# lcd_breakout.net
KiCad netlist of a schematic drawn in Altium Designer
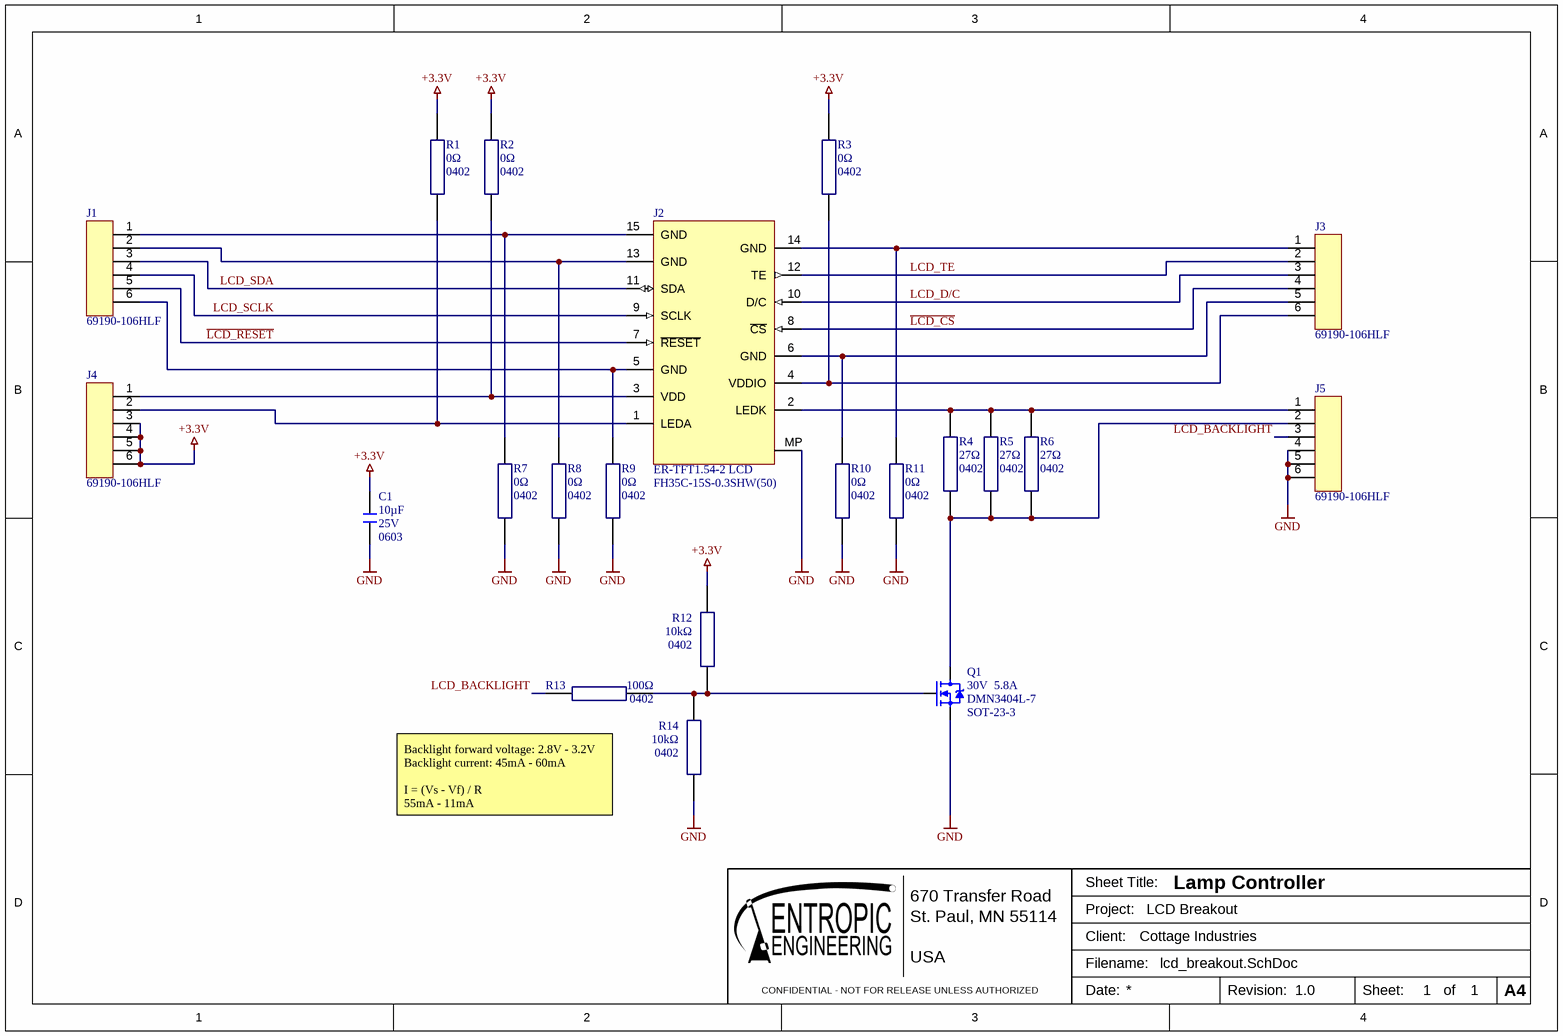
[diagram p0: lcd_breakout.SchDoc]

(export (version "E")
  (design (tool "Eeschema 10.0.6"))
  (components
    (comp (ref "C1")
      (value "10µF")
      (footprint "0603_capacitor")
      (description "10 µF, 25 V, X5R, 0603 Chip capacitor")
      (fields
        (field (name "MANUFACTURER") "Samsung")
        (field (name "CASE/PACKAGE") "0603")
        (field (name "TOLERANCE") "20%")
        (field (name "VOLTAGE RATING") "25V")
      )
      (libsource (lib "lamp_controller") (part "CL10A106MA8NRNC"))
    )
    (comp (ref "J1")
      (value "*")
      (footprint "69190-106HLF")
      (description "6-Pin 0.1\" unshrouded header pins")
      (fields
        (field (name "MANUFACTURER") "Amphenol ICC / FCI")
        (field (name "MANUFACTURER PART NUMBER") "69190-106HLF")
      )
      (libsource (lib "") (part "69190-106HLF_1"))
    )
    (comp (ref "J2")
      (value "ER-TFT1.54-2 LCD")
      (footprint "FH35C-15S-0.3SHW(50)")
      (description "ER-TFT1.54-2 1.54\" IPS LCD, 240x240, ST7789 controller, FH35C-15S-0.3SHW(50) connector")
      (fields
        (field (name "MANUFACTURER") "HRS")
        (field (name "MANUFACTURER PART NUMBER") "FH35C-15S-0.3SHW(50)")
      )
      (libsource (lib "lamp_controller") (part "LCD Connector"))
    )
    (comp (ref "J3")
      (value "*")
      (footprint "69190-106HLF")
      (description "6-Pin 0.1\" unshrouded header pins")
      (fields
        (field (name "MANUFACTURER") "Amphenol ICC / FCI")
        (field (name "MANUFACTURER PART NUMBER") "69190-106HLF")
      )
      (libsource (lib "lamp_controller") (part "69190-106HLF"))
    )
    (comp (ref "J4")
      (value "*")
      (footprint "69190-106HLF")
      (description "6-Pin 0.1\" unshrouded header pins")
      (fields
        (field (name "MANUFACTURER") "Amphenol ICC / FCI")
        (field (name "MANUFACTURER PART NUMBER") "69190-106HLF")
      )
      (libsource (lib "") (part "69190-106HLF_1"))
    )
    (comp (ref "J5")
      (value "*")
      (footprint "69190-106HLF")
      (description "6-Pin 0.1\" unshrouded header pins")
      (fields
        (field (name "MANUFACTURER") "Amphenol ICC / FCI")
        (field (name "MANUFACTURER PART NUMBER") "69190-106HLF")
      )
      (libsource (lib "lamp_controller") (part "69190-106HLF"))
    )
    (comp (ref "Q1")
      (value "DMN3404L-7")
      (footprint "SOT-23-3")
      (description "N-FET, 30 V, 5.8 A, SOT-23-3")
      (fields
        (field (name "MANUFACTURER") "Diodes")
        (field (name "PACKAGE") "SOT-23-3")
        (field (name "DS BREAKDOWN VOLTAGE-MIN") "30V")
        (field (name "DRAIN CURRENT-MAX (ID)") "5.8A")
        (field (name "MANUFACTURER PART NUMBER") "DMN3404L-7")
      )
      (libsource (lib "lamp_controller") (part "DMN3404L-7"))
    )
    (comp (ref "R1")
      (value "RMCF0402ZT0R00")
      (footprint "0402_resistor")
      (description "0 Ω, 0402 Jumper")
      (fields
        (field (name "MANUFACTURER") "Stackpole Electronics")
        (field (name "HOUSE_PART_NUMBER") "JP-0402-001")
        (field (name "RESISTANCE") "0Ω")
        (field (name "CASE/PACKAGE") "0402")
      )
      (libsource (lib "lamp_controller") (part "RMCF0402ZT0R00"))
    )
    (comp (ref "R2")
      (value "RMCF0402ZT0R00")
      (footprint "0402_resistor")
      (description "0 Ω, 0402 Jumper")
      (fields
        (field (name "MANUFACTURER") "Stackpole Electronics")
        (field (name "HOUSE_PART_NUMBER") "JP-0402-001")
        (field (name "RESISTANCE") "0Ω")
        (field (name "CASE/PACKAGE") "0402")
      )
      (libsource (lib "lamp_controller") (part "RMCF0402ZT0R00"))
    )
    (comp (ref "R3")
      (value "RMCF0402ZT0R00")
      (footprint "0402_resistor")
      (description "0 Ω, 0402 Jumper")
      (fields
        (field (name "MANUFACTURER") "Stackpole Electronics")
        (field (name "HOUSE_PART_NUMBER") "JP-0402-001")
        (field (name "RESISTANCE") "0Ω")
        (field (name "CASE/PACKAGE") "0402")
      )
      (libsource (lib "lamp_controller") (part "RMCF0402ZT0R00"))
    )
    (comp (ref "R4")
      (value "RMCF0402FT27R0")
      (footprint "0402_resistor")
      (description "27 Ω, 0402 Chip resistor")
      (fields
        (field (name "MANUFACTURER") "Stackpole Electronics")
        (field (name "TOLERANCE") "1%")
        (field (name "RESISTANCE") "27Ω")
        (field (name "SIZE CODE") "0402")
      )
      (libsource (lib "lamp_controller") (part "RMCF0402FT27R0"))
    )
    (comp (ref "R5")
      (value "RMCF0402FT27R0")
      (footprint "0402_resistor")
      (description "27 Ω, 0402 Chip resistor")
      (fields
        (field (name "MANUFACTURER") "Stackpole Electronics")
        (field (name "TOLERANCE") "1%")
        (field (name "RESISTANCE") "27Ω")
        (field (name "SIZE CODE") "0402")
      )
      (libsource (lib "lamp_controller") (part "RMCF0402FT27R0"))
    )
    (comp (ref "R6")
      (value "RMCF0402FT27R0")
      (footprint "0402_resistor")
      (description "27 Ω, 0402 Chip resistor")
      (fields
        (field (name "MANUFACTURER") "Stackpole Electronics")
        (field (name "TOLERANCE") "1%")
        (field (name "RESISTANCE") "27Ω")
        (field (name "SIZE CODE") "0402")
      )
      (libsource (lib "lamp_controller") (part "RMCF0402FT27R0"))
    )
    (comp (ref "R7")
      (value "RMCF0402ZT0R00")
      (footprint "0402_resistor")
      (description "0 Ω, 0402 Jumper")
      (fields
        (field (name "MANUFACTURER") "Stackpole Electronics")
        (field (name "HOUSE_PART_NUMBER") "JP-0402-001")
        (field (name "RESISTANCE") "0Ω")
        (field (name "CASE/PACKAGE") "0402")
      )
      (libsource (lib "lamp_controller") (part "RMCF0402ZT0R00"))
    )
    (comp (ref "R8")
      (value "RMCF0402ZT0R00")
      (footprint "0402_resistor")
      (description "0 Ω, 0402 Jumper")
      (fields
        (field (name "MANUFACTURER") "Stackpole Electronics")
        (field (name "HOUSE_PART_NUMBER") "JP-0402-001")
        (field (name "RESISTANCE") "0Ω")
        (field (name "CASE/PACKAGE") "0402")
      )
      (libsource (lib "lamp_controller") (part "RMCF0402ZT0R00"))
    )
    (comp (ref "R9")
      (value "RMCF0402ZT0R00")
      (footprint "0402_resistor")
      (description "0 Ω, 0402 Jumper")
      (fields
        (field (name "MANUFACTURER") "Stackpole Electronics")
        (field (name "HOUSE_PART_NUMBER") "JP-0402-001")
        (field (name "RESISTANCE") "0Ω")
        (field (name "CASE/PACKAGE") "0402")
      )
      (libsource (lib "lamp_controller") (part "RMCF0402ZT0R00"))
    )
    (comp (ref "R10")
      (value "RMCF0402ZT0R00")
      (footprint "0402_resistor")
      (description "0 Ω, 0402 Jumper")
      (fields
        (field (name "MANUFACTURER") "Stackpole Electronics")
        (field (name "HOUSE_PART_NUMBER") "JP-0402-001")
        (field (name "RESISTANCE") "0Ω")
        (field (name "CASE/PACKAGE") "0402")
      )
      (libsource (lib "lamp_controller") (part "RMCF0402ZT0R00"))
    )
    (comp (ref "R11")
      (value "RMCF0402ZT0R00")
      (footprint "0402_resistor")
      (description "0 Ω, 0402 Jumper")
      (fields
        (field (name "MANUFACTURER") "Stackpole Electronics")
        (field (name "HOUSE_PART_NUMBER") "JP-0402-001")
        (field (name "RESISTANCE") "0Ω")
        (field (name "CASE/PACKAGE") "0402")
      )
      (libsource (lib "lamp_controller") (part "RMCF0402ZT0R00"))
    )
    (comp (ref "R12")
      (value "RMCF0402FT10K0")
      (footprint "0402_resistor")
      (description "10 kΩ, 0402 Chip resistor")
      (fields
        (field (name "MANUFACTURER") "Stackpole Electronics")
        (field (name "TOLERANCE") "1%")
        (field (name "CASE CODE (IMPERIAL)") "0402")
        (field (name "RESISTANCE") "10kΩ")
      )
      (libsource (lib "lamp_controller") (part "RMCF0402FT10K0"))
    )
    (comp (ref "R13")
      (value "RMCF0402FT100R")
      (footprint "0402_resistor")
      (description "100 Ω, 0402 Chip resistor")
      (fields
        (field (name "MANUFACTURER") "Stackpole Electronics")
        (field (name "TOLERANCE") "1%")
        (field (name "CASE CODE (IMPERIAL)") "0402")
        (field (name "RESISTANCE") "100Ω")
      )
      (libsource (lib "lamp_controller") (part "RMCF0402FT100R"))
    )
    (comp (ref "R14")
      (value "RMCF0402FT10K0")
      (footprint "0402_resistor")
      (description "10 kΩ, 0402 Chip resistor")
      (fields
        (field (name "MANUFACTURER") "Stackpole Electronics")
        (field (name "TOLERANCE") "1%")
        (field (name "CASE CODE (IMPERIAL)") "0402")
        (field (name "RESISTANCE") "10kΩ")
      )
      (libsource (lib "lamp_controller") (part "RMCF0402FT10K0"))
    )
  )
  (nets
    (net (code "1") (name "+3.3V") (class "Default")
      (node (ref "C1") (pin "2") (pinfunction "2_2") (pintype "passive"))
      (node (ref "J4") (pin "3") (pintype "passive"))
      (node (ref "J4") (pin "4") (pintype "passive"))
      (node (ref "J4") (pin "5") (pintype "passive"))
      (node (ref "J4") (pin "6") (pintype "passive"))
      (node (ref "R1") (pin "2") (pinfunction "2_2") (pintype "passive"))
      (node (ref "R12") (pin "1") (pinfunction "1_1") (pintype "passive"))
      (node (ref "R2") (pin "2") (pinfunction "2_2") (pintype "passive"))
      (node (ref "R3") (pin "2") (pinfunction "2_2") (pintype "passive"))
    )
    (net (code "2") (name "/LCD_BACKLIGHT") (class "Default")
      (node (ref "J5") (pin "3") (pintype "passive"))
      (node (ref "R13") (pin "1") (pinfunction "1_1") (pintype "passive"))
    )
    (net (code "3") (name "/LCD_CS") (class "Default")
      (node (ref "J2") (pin "8") (pinfunction "CS_8") (pintype "input"))
      (node (ref "J3") (pin "4") (pintype "passive"))
    )
    (net (code "4") (name "/LCD_D{slash}C") (class "Default")
      (node (ref "J2") (pin "10") (pinfunction "D/C_10") (pintype "input"))
      (node (ref "J3") (pin "3") (pintype "passive"))
    )
    (net (code "5") (name "/LCD_RESET") (class "Default")
      (node (ref "J1") (pin "5") (pintype "passive"))
      (node (ref "J2") (pin "7") (pinfunction "RESET_7") (pintype "input"))
    )
    (net (code "6") (name "/LCD_SCLK") (class "Default")
      (node (ref "J1") (pin "4") (pintype "passive"))
      (node (ref "J2") (pin "9") (pinfunction "SCLK_9") (pintype "input"))
    )
    (net (code "7") (name "/LCD_SDA") (class "Default")
      (node (ref "J1") (pin "3") (pintype "passive"))
      (node (ref "J2") (pin "11") (pinfunction "SDA_11") (pintype "bidirectional"))
    )
    (net (code "8") (name "/LCD_TE") (class "Default")
      (node (ref "J2") (pin "12") (pinfunction "TE_12") (pintype "output"))
      (node (ref "J3") (pin "2") (pintype "passive"))
    )
    (net (code "9") (name "GND") (class "Default")
      (node (ref "C1") (pin "1") (pinfunction "1_1") (pintype "passive"))
      (node (ref "J2") (pin "MP") (pintype "passive"))
      (node (ref "J5") (pin "4") (pintype "passive"))
      (node (ref "J5") (pin "5") (pintype "passive"))
      (node (ref "J5") (pin "6") (pintype "passive"))
      (node (ref "Q1") (pin "2") (pinfunction "S_2") (pintype "passive"))
      (node (ref "R10") (pin "1") (pinfunction "1_1") (pintype "passive"))
      (node (ref "R11") (pin "1") (pinfunction "1_1") (pintype "passive"))
      (node (ref "R14") (pin "2") (pinfunction "2_2") (pintype "passive"))
      (node (ref "R7") (pin "1") (pinfunction "1_1") (pintype "passive"))
      (node (ref "R8") (pin "1") (pinfunction "1_1") (pintype "passive"))
      (node (ref "R9") (pin "1") (pinfunction "1_1") (pintype "passive"))
    )
    (net (code "10") (name "Net-(J1-Pad1)") (class "Default")
      (node (ref "J1") (pin "1") (pintype "passive"))
      (node (ref "J2") (pin "15") (pinfunction "GND_15") (pintype "power_in"))
      (node (ref "R7") (pin "2") (pinfunction "2_2") (pintype "passive"))
    )
    (net (code "11") (name "Net-(J1-Pad2)") (class "Default")
      (node (ref "J1") (pin "2") (pintype "passive"))
      (node (ref "J2") (pin "13") (pinfunction "GND_13") (pintype "power_in"))
      (node (ref "R8") (pin "2") (pinfunction "2_2") (pintype "passive"))
    )
    (net (code "12") (name "Net-(J1-Pad6)") (class "Default")
      (node (ref "J1") (pin "6") (pintype "passive"))
      (node (ref "J2") (pin "5") (pinfunction "GND_5") (pintype "power_in"))
      (node (ref "R9") (pin "2") (pinfunction "2_2") (pintype "passive"))
    )
    (net (code "13") (name "Net-(J2-GND-Pad6)") (class "Default")
      (node (ref "J2") (pin "6") (pinfunction "GND_6") (pintype "power_in"))
      (node (ref "J3") (pin "5") (pintype "passive"))
      (node (ref "R10") (pin "2") (pinfunction "2_2") (pintype "passive"))
    )
    (net (code "14") (name "Net-(J2-GND-Pad14)") (class "Default")
      (node (ref "J2") (pin "14") (pinfunction "GND_14") (pintype "power_in"))
      (node (ref "J3") (pin "1") (pintype "passive"))
      (node (ref "R11") (pin "2") (pinfunction "2_2") (pintype "passive"))
    )
    (net (code "15") (name "Net-(J2-LEDA)") (class "Default")
      (node (ref "J2") (pin "1") (pinfunction "LEDA_1") (pintype "passive"))
      (node (ref "J4") (pin "2") (pintype "passive"))
      (node (ref "R1") (pin "1") (pinfunction "1_1") (pintype "passive"))
    )
    (net (code "16") (name "Net-(J2-LEDK)") (class "Default")
      (node (ref "J2") (pin "2") (pinfunction "LEDK_2") (pintype "passive"))
      (node (ref "J5") (pin "1") (pintype "passive"))
      (node (ref "R4") (pin "1") (pinfunction "1_1") (pintype "passive"))
      (node (ref "R5") (pin "1") (pinfunction "1_1") (pintype "passive"))
      (node (ref "R6") (pin "1") (pinfunction "1_1") (pintype "passive"))
    )
    (net (code "17") (name "Net-(J2-VDD)") (class "Default")
      (node (ref "J2") (pin "3") (pinfunction "VDD_3") (pintype "power_in"))
      (node (ref "J4") (pin "1") (pintype "passive"))
      (node (ref "R2") (pin "1") (pinfunction "1_1") (pintype "passive"))
    )
    (net (code "18") (name "Net-(J2-VDDIO)") (class "Default")
      (node (ref "J2") (pin "4") (pinfunction "VDDIO_4") (pintype "power_in"))
      (node (ref "J3") (pin "6") (pintype "passive"))
      (node (ref "R3") (pin "1") (pinfunction "1_1") (pintype "passive"))
    )
    (net (code "19") (name "Net-(Q1-D)") (class "Default")
      (node (ref "J5") (pin "2") (pintype "passive"))
      (node (ref "Q1") (pin "3") (pinfunction "D_3") (pintype "passive"))
      (node (ref "R4") (pin "2") (pinfunction "2_2") (pintype "passive"))
      (node (ref "R5") (pin "2") (pinfunction "2_2") (pintype "passive"))
      (node (ref "R6") (pin "2") (pinfunction "2_2") (pintype "passive"))
    )
    (net (code "20") (name "Net-(Q1-G)") (class "Default")
      (node (ref "Q1") (pin "1") (pinfunction "G_1") (pintype "passive"))
      (node (ref "R12") (pin "2") (pinfunction "2_2") (pintype "passive"))
      (node (ref "R13") (pin "2") (pinfunction "2_2") (pintype "passive"))
      (node (ref "R14") (pin "1") (pinfunction "1_1") (pintype "passive"))
    )
  )
)
